# SparkFun_FM_Tuner_Basic_Breakout.net
KiCad netlist of a schematic drawn in EAGLE
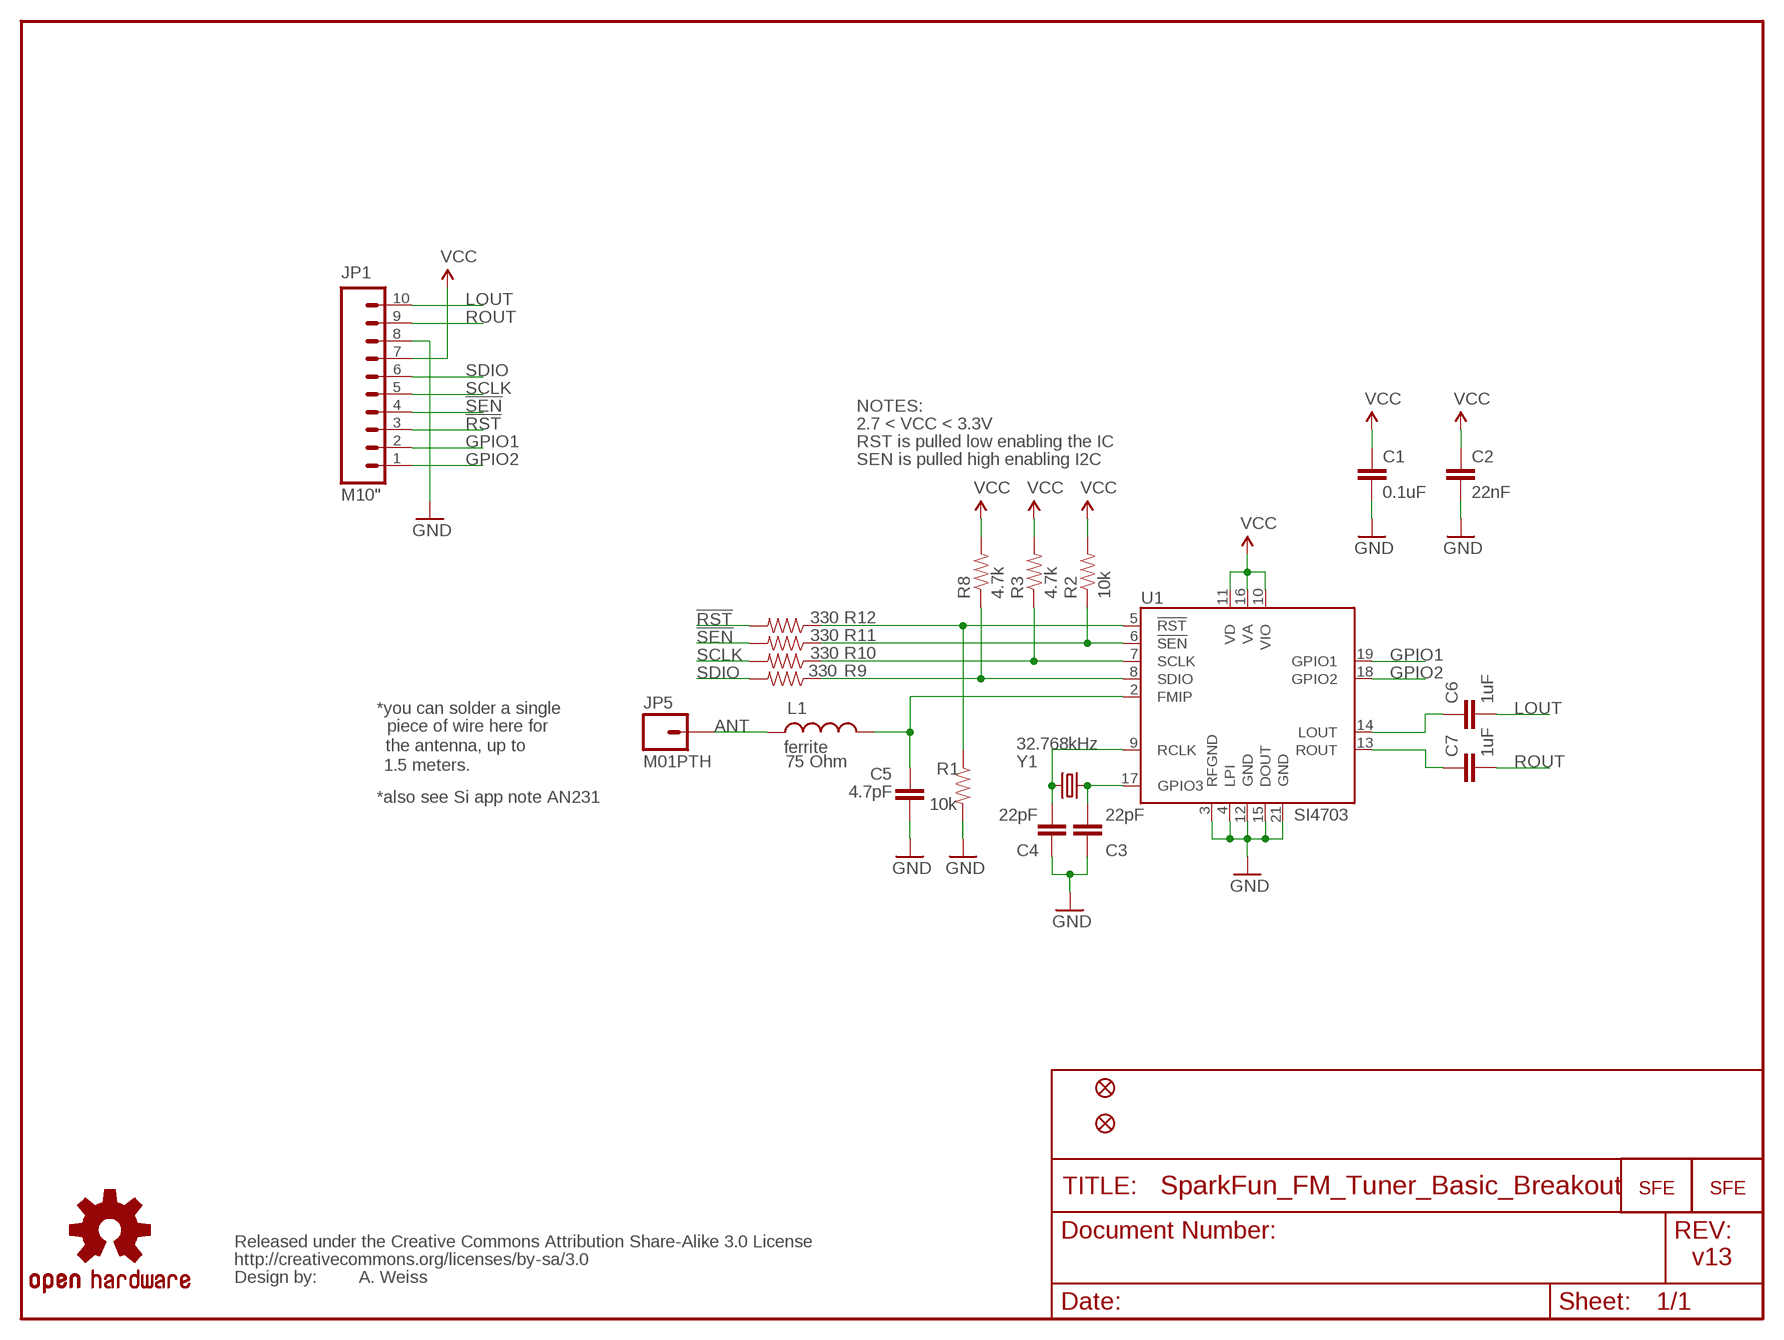
[diagram p0: schematic, sheet 1]

(export (version "E")
  (design (tool "Eeschema 10.0.6"))
  (components
    (comp (ref "C1")
      (value "0.1uF")
      (footprint "eagle-import:0402-CAP")
      (libsource (lib "eagle-import") (part "CAP0402-CAP"))
    )
    (comp (ref "C2")
      (value "22nF")
      (footprint "eagle-import:0402-CAP")
      (libsource (lib "eagle-import") (part "CAP0402-CAP"))
    )
    (comp (ref "C3")
      (value "22pF")
      (footprint "eagle-import:0402-CAP")
      (libsource (lib "eagle-import") (part "CAP0402-CAP"))
    )
    (comp (ref "C4")
      (value "22pF")
      (footprint "eagle-import:0402-CAP")
      (libsource (lib "eagle-import") (part "CAP0402-CAP"))
    )
    (comp (ref "C5")
      (value "4.7pF")
      (footprint "eagle-import:0402-CAP")
      (libsource (lib "eagle-import") (part "CAP0402-CAP"))
    )
    (comp (ref "C6")
      (value "1uF")
      (footprint "eagle-import:0402-CAP")
      (libsource (lib "eagle-import") (part "CAP0402-CAP"))
    )
    (comp (ref "C7")
      (value "1uF")
      (footprint "eagle-import:0402-CAP")
      (libsource (lib "eagle-import") (part "CAP0402-CAP"))
    )
    (comp (ref "JP1")
      (value "M10\"")
      (footprint "eagle-import:1X10")
      (libsource (lib "eagle-import") (part "M10{dblquote}"))
    )
    (comp (ref "JP2")
      (value "LOGO-SFENW2")
      (footprint "eagle-import:SFE-NEW-WEB")
      (libsource (lib "eagle-import") (part "LOGO-SFENW2"))
    )
    (comp (ref "JP3")
      (value "LOGO-SFESK")
      (footprint "eagle-import:SFE-LOGO-FLAME")
      (libsource (lib "eagle-import") (part "LOGO-SFESK"))
    )
    (comp (ref "JP4")
      (value "FIDUCIALUFIDUCIAL")
      (footprint "eagle-import:MICRO-FIDUCIAL")
      (libsource (lib "eagle-import") (part "FIDUCIALUFIDUCIAL"))
    )
    (comp (ref "JP5")
      (value "M01PTH")
      (footprint "eagle-import:1X01")
      (libsource (lib "eagle-import") (part "M01PTH"))
    )
    (comp (ref "JP6")
      (value "FIDUCIALUFIDUCIAL")
      (footprint "eagle-import:MICRO-FIDUCIAL")
      (libsource (lib "eagle-import") (part "FIDUCIALUFIDUCIAL"))
    )
    (comp (ref "L1")
      (value "ferrite")
      (footprint "eagle-import:C0402")
      (fields (field (name "RESISTANCE") "75 Ohm"))
      (libsource (lib "eagle-import") (part "INDUCTOR0402"))
    )
    (comp (ref "R1")
      (value "10k")
      (footprint "eagle-import:0402-RES")
      (libsource (lib "eagle-import") (part "RESISTOR0402-RES"))
    )
    (comp (ref "R2")
      (value "10k")
      (footprint "eagle-import:0402-RES")
      (libsource (lib "eagle-import") (part "RESISTOR0402-RES"))
    )
    (comp (ref "R3")
      (value "4.7k")
      (footprint "eagle-import:0402-RES")
      (libsource (lib "eagle-import") (part "RESISTOR0402-RES"))
    )
    (comp (ref "R8")
      (value "4.7k")
      (footprint "eagle-import:0402-RES")
      (libsource (lib "eagle-import") (part "RESISTOR0402-RES"))
    )
    (comp (ref "R9")
      (value "330")
      (footprint "eagle-import:0402-RES")
      (libsource (lib "eagle-import") (part "RESISTOR0402-RES"))
    )
    (comp (ref "R10")
      (value "330")
      (footprint "eagle-import:0402-RES")
      (libsource (lib "eagle-import") (part "RESISTOR0402-RES"))
    )
    (comp (ref "R11")
      (value "330")
      (footprint "eagle-import:0402-RES")
      (libsource (lib "eagle-import") (part "RESISTOR0402-RES"))
    )
    (comp (ref "R12")
      (value "330")
      (footprint "eagle-import:0402-RES")
      (libsource (lib "eagle-import") (part "RESISTOR0402-RES"))
    )
    (comp (ref "U$1")
      (value "CREATIVE_COMMONS")
      (footprint "eagle-import:CREATIVE_COMMONS")
      (libsource (lib "eagle-import") (part "CREATIVE_COMMONS"))
    )
    (comp (ref "U$3")
      (value "OSHW-LOGOS")
      (footprint "eagle-import:OSHW-LOGO-S")
      (libsource (lib "eagle-import") (part "OSHW-LOGOS"))
    )
    (comp (ref "U1")
      (value "SI4703")
      (footprint "eagle-import:SPARKFUN_SI470X")
      (libsource (lib "eagle-import") (part "SPARKFUN_SI470X"))
    )
    (comp (ref "Y1")
      (value "32.768kHz")
      (footprint "eagle-import:CRYSTAL-32KHZ-SMD")
      (libsource (lib "eagle-import") (part "CRYSTAL32-SMD"))
    )
  )
  (nets
    (net (code "1") (name "/ANT") (class "Default")
      (node (ref "JP5") (pin "1") (pinfunction "1_1") (pintype "passive"))
      (node (ref "L1") (pin "1") (pinfunction "1_1") (pintype "passive"))
    )
    (net (code "2") (name "/GPIO1") (class "Default")
      (node (ref "JP1") (pin "2") (pinfunction "2_2") (pintype "passive"))
      (node (ref "U1") (pin "19") (pinfunction "GPIO1_19") (pintype "bidirectional"))
    )
    (net (code "3") (name "/GPIO2") (class "Default")
      (node (ref "JP1") (pin "1") (pinfunction "1_1") (pintype "passive"))
      (node (ref "U1") (pin "18") (pinfunction "GPIO2_18") (pintype "bidirectional"))
    )
    (net (code "4") (name "/LOUT") (class "Default")
      (node (ref "C6") (pin "2") (pinfunction "2_2") (pintype "passive"))
      (node (ref "JP1") (pin "10") (pinfunction "10_10") (pintype "passive"))
    )
    (net (code "5") (name "/ROUT") (class "Default")
      (node (ref "C7") (pin "2") (pinfunction "2_2") (pintype "passive"))
      (node (ref "JP1") (pin "9") (pinfunction "9_9") (pintype "passive"))
    )
    (net (code "6") (name "/SCLK") (class "Default")
      (node (ref "JP1") (pin "5") (pinfunction "5_5") (pintype "passive"))
      (node (ref "R10") (pin "2") (pinfunction "2_2") (pintype "passive"))
    )
    (net (code "7") (name "/SDIO") (class "Default")
      (node (ref "JP1") (pin "6") (pinfunction "6_6") (pintype "passive"))
      (node (ref "R9") (pin "2") (pinfunction "2_2") (pintype "passive"))
    )
    (net (code "8") (name "/~{RST}") (class "Default")
      (node (ref "JP1") (pin "3") (pinfunction "3_3") (pintype "passive"))
      (node (ref "R12") (pin "2") (pinfunction "2_2") (pintype "passive"))
    )
    (net (code "9") (name "/~{SEN}") (class "Default")
      (node (ref "JP1") (pin "4") (pinfunction "4_4") (pintype "passive"))
      (node (ref "R11") (pin "2") (pinfunction "2_2") (pintype "passive"))
    )
    (net (code "10") (name "GND") (class "Default")
      (node (ref "C1") (pin "2") (pinfunction "2_2") (pintype "passive"))
      (node (ref "C2") (pin "2") (pinfunction "2_2") (pintype "passive"))
      (node (ref "C3") (pin "1") (pinfunction "1_1") (pintype "passive"))
      (node (ref "C4") (pin "1") (pinfunction "1_1") (pintype "passive"))
      (node (ref "C5") (pin "2") (pinfunction "2_2") (pintype "passive"))
      (node (ref "JP1") (pin "8") (pinfunction "8_8") (pintype "passive"))
      (node (ref "R1") (pin "2") (pinfunction "2_2") (pintype "passive"))
      (node (ref "U1") (pin "12") (pinfunction "GND_12") (pintype "bidirectional"))
      (node (ref "U1") (pin "15") (pinfunction "DOUT_15") (pintype "bidirectional"))
      (node (ref "U1") (pin "21") (pinfunction "GND_21") (pintype "bidirectional"))
      (node (ref "U1") (pin "3") (pinfunction "RFGND_3") (pintype "bidirectional"))
      (node (ref "U1") (pin "4") (pinfunction "LPI_4") (pintype "bidirectional"))
    )
    (net (code "11") (name "Net-(U1-FMIP)") (class "Default")
      (node (ref "C5") (pin "1") (pinfunction "1_1") (pintype "passive"))
      (node (ref "L1") (pin "2") (pinfunction "2_2") (pintype "passive"))
      (node (ref "U1") (pin "2") (pinfunction "FMIP_2") (pintype "bidirectional"))
    )
    (net (code "12") (name "Net-(U1-GPIO3)") (class "Default")
      (node (ref "C3") (pin "2") (pinfunction "2_2") (pintype "passive"))
      (node (ref "U1") (pin "17") (pinfunction "GPIO3_17") (pintype "bidirectional"))
      (node (ref "Y1") (pin "X1") (pinfunction "1_X1") (pintype "passive"))
    )
    (net (code "13") (name "Net-(U1-LOUT)") (class "Default")
      (node (ref "C6") (pin "1") (pinfunction "1_1") (pintype "passive"))
      (node (ref "U1") (pin "14") (pinfunction "LOUT_14") (pintype "bidirectional"))
    )
    (net (code "14") (name "Net-(U1-RCLK)") (class "Default")
      (node (ref "C4") (pin "2") (pinfunction "2_2") (pintype "passive"))
      (node (ref "U1") (pin "9") (pinfunction "RCLK_9") (pintype "bidirectional"))
      (node (ref "Y1") (pin "X2") (pinfunction "2_X2") (pintype "passive"))
    )
    (net (code "15") (name "Net-(U1-ROUT)") (class "Default")
      (node (ref "C7") (pin "1") (pinfunction "1_1") (pintype "passive"))
      (node (ref "U1") (pin "13") (pinfunction "ROUT_13") (pintype "bidirectional"))
    )
    (net (code "16") (name "Net-(U1-SCLK)") (class "Default")
      (node (ref "R10") (pin "1") (pinfunction "1_1") (pintype "passive"))
      (node (ref "R3") (pin "1") (pinfunction "1_1") (pintype "passive"))
      (node (ref "U1") (pin "7") (pinfunction "SCLK_7") (pintype "bidirectional"))
    )
    (net (code "17") (name "Net-(U1-SDIO)") (class "Default")
      (node (ref "R8") (pin "1") (pinfunction "1_1") (pintype "passive"))
      (node (ref "R9") (pin "1") (pinfunction "1_1") (pintype "passive"))
      (node (ref "U1") (pin "8") (pinfunction "SDIO_8") (pintype "bidirectional"))
    )
    (net (code "18") (name "Net-(U1-~{RST})") (class "Default")
      (node (ref "R1") (pin "1") (pinfunction "1_1") (pintype "passive"))
      (node (ref "R12") (pin "1") (pinfunction "1_1") (pintype "passive"))
      (node (ref "U1") (pin "5") (pinfunction "~{RST}_5") (pintype "bidirectional"))
    )
    (net (code "19") (name "Net-(U1-~{SEN})") (class "Default")
      (node (ref "R11") (pin "1") (pinfunction "1_1") (pintype "passive"))
      (node (ref "R2") (pin "1") (pinfunction "1_1") (pintype "passive"))
      (node (ref "U1") (pin "6") (pinfunction "~{SEN}_6") (pintype "bidirectional"))
    )
    (net (code "20") (name "VCC") (class "Default")
      (node (ref "C1") (pin "1") (pinfunction "1_1") (pintype "passive"))
      (node (ref "C2") (pin "1") (pinfunction "1_1") (pintype "passive"))
      (node (ref "JP1") (pin "7") (pinfunction "7_7") (pintype "passive"))
      (node (ref "R2") (pin "2") (pinfunction "2_2") (pintype "passive"))
      (node (ref "R3") (pin "2") (pinfunction "2_2") (pintype "passive"))
      (node (ref "R8") (pin "2") (pinfunction "2_2") (pintype "passive"))
      (node (ref "U1") (pin "10") (pinfunction "VIO_10") (pintype "bidirectional"))
      (node (ref "U1") (pin "11") (pinfunction "VD_11") (pintype "bidirectional"))
      (node (ref "U1") (pin "16") (pinfunction "VA_16") (pintype "bidirectional"))
    )
  )
)
